# melexis_board.net
KiCad netlist of a schematic drawn in EAGLE
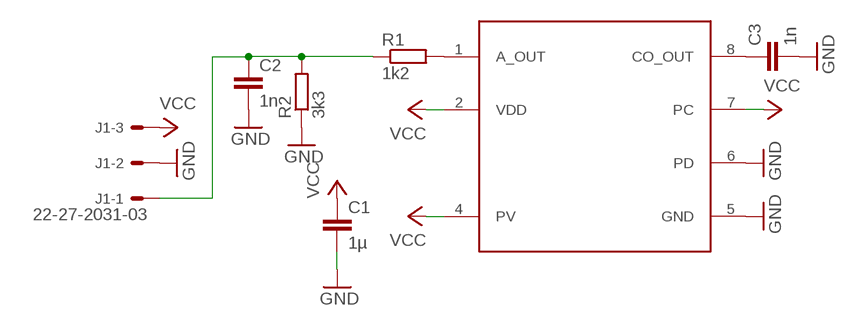
[diagram p0: schematic, sheet 1]

(export (version "E")
  (design (tool "Eeschema 10.0.6"))
  (components
    (comp (ref "C1")
      (value "1µ")
      (footprint "eagle-import:C025-024X044")
      (libsource (lib "eagle-import") (part "C-EU025-024X044"))
    )
    (comp (ref "C2")
      (value "1n")
      (footprint "eagle-import:C025-024X044")
      (libsource (lib "eagle-import") (part "C-EU025-024X044"))
    )
    (comp (ref "C3")
      (value "1n")
      (footprint "eagle-import:C025-024X044")
      (libsource (lib "eagle-import") (part "C-EU025-024X044"))
    )
    (comp (ref "IC1")
      (value "MLX91205")
      (footprint "eagle-import:SO-08")
      (libsource (lib "eagle-import") (part "MLX91205"))
    )
    (comp (ref "J1")
      (value "22-27-2031-03")
      (footprint "eagle-import:6410-03")
      (libsource (lib "eagle-import") (part "22-?-0327-2031"))
    )
    (comp (ref "R1")
      (value "1k2")
      (footprint "eagle-import:0204V")
      (libsource (lib "eagle-import") (part "R-EU_0204/2V"))
    )
    (comp (ref "R2")
      (value "3k3")
      (footprint "eagle-import:0204V")
      (libsource (lib "eagle-import") (part "R-EU_0204/2V"))
    )
  )
  (nets
    (net (code "1") (name "GND") (class "Default")
      (node (ref "C1") (pin "2") (pinfunction "2_2") (pintype "passive"))
      (node (ref "C2") (pin "2") (pinfunction "2_2") (pintype "passive"))
      (node (ref "C3") (pin "2") (pinfunction "2_2") (pintype "passive"))
      (node (ref "IC1") (pin "5") (pinfunction "GND_5") (pintype "bidirectional"))
      (node (ref "IC1") (pin "6") (pinfunction "PD_6") (pintype "bidirectional"))
      (node (ref "J1") (pin "2") (pinfunction "S_2") (pintype "passive"))
      (node (ref "R2") (pin "1") (pinfunction "1_1") (pintype "passive"))
    )
    (net (code "2") (name "Net-(IC1-A_OUT)") (class "Default")
      (node (ref "IC1") (pin "1") (pinfunction "A_OUT_1") (pintype "bidirectional"))
      (node (ref "R1") (pin "2") (pinfunction "2_2") (pintype "passive"))
    )
    (net (code "3") (name "Net-(IC1-CO_OUT)") (class "Default")
      (node (ref "C3") (pin "1") (pinfunction "1_1") (pintype "passive"))
      (node (ref "IC1") (pin "8") (pinfunction "CO_OUT_8") (pintype "bidirectional"))
    )
    (net (code "4") (name "Net-(J1A-S)") (class "Default")
      (node (ref "C2") (pin "1") (pinfunction "1_1") (pintype "passive"))
      (node (ref "J1") (pin "1") (pinfunction "S_1") (pintype "passive"))
      (node (ref "R1") (pin "1") (pinfunction "1_1") (pintype "passive"))
      (node (ref "R2") (pin "2") (pinfunction "2_2") (pintype "passive"))
    )
    (net (code "5") (name "VCC") (class "Default")
      (node (ref "C1") (pin "1") (pinfunction "1_1") (pintype "passive"))
      (node (ref "IC1") (pin "2") (pinfunction "VDD_2") (pintype "bidirectional"))
      (node (ref "IC1") (pin "4") (pinfunction "PV_4") (pintype "bidirectional"))
      (node (ref "IC1") (pin "7") (pinfunction "PC_7") (pintype "bidirectional"))
      (node (ref "J1") (pin "3") (pinfunction "S_3") (pintype "passive"))
    )
  )
)
